# Microphone.net
KiCad netlist of a schematic drawn in Altium Designer
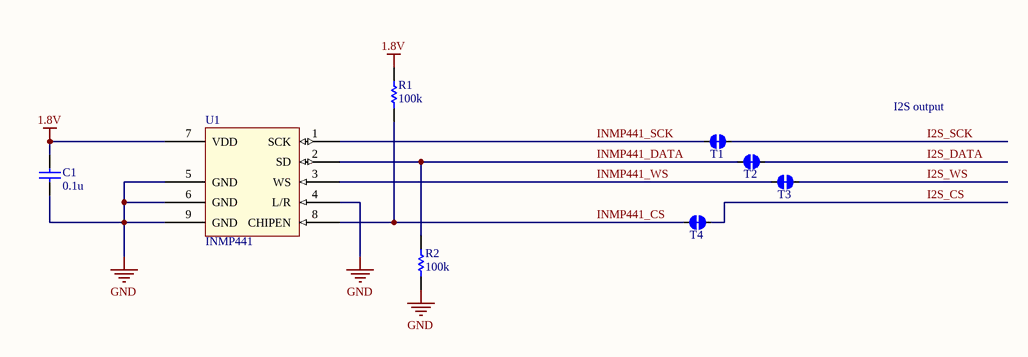
[diagram p0: Microphone.SchDoc]

(export (version "E")
  (design (tool "Eeschema 10.0.6"))
  (components
    (comp (ref "C1")
      (value "0.1u")
      (footprint "CAP0201")
      (description "Chip capacitor")
      (fields (field (name "TOLERANCE") "10%") (field (name "VOLTAGE") "6.3"))
      (libsource (lib "Hello") (part "C_0.1u_10_6.3_X5R_0201"))
    )
    (comp (ref "R1")
      (value "100k")
      (footprint "RES0201")
      (description "Chip Resistor")
      (fields (field (name "TOLERANCE") "5 %") (field (name "POWER") "0.05 W"))
      (libsource (lib "Hello") (part "R_100k_5_0.05_0201"))
    )
    (comp (ref "R2")
      (value "100k")
      (footprint "RES0201")
      (description "Chip Resistor")
      (fields (field (name "TOLERANCE") "5 %") (field (name "POWER") "0.05 W"))
      (libsource (lib "Hello") (part "R_100k_5_0.05_0201"))
    )
    (comp (ref "T1")
      (value "Solderbridge_short_1mm")
      (footprint "Solderbridge_short_1mm")
      (description "Solderbridge, shorted")
      (libsource (lib "Hello") (part "Solderbridge_short_1mm"))
    )
    (comp (ref "T2")
      (value "Solderbridge_short_1mm")
      (footprint "Solderbridge_short_1mm")
      (description "Solderbridge, shorted")
      (libsource (lib "Hello") (part "Solderbridge_short_1mm"))
    )
    (comp (ref "T3")
      (value "Solderbridge_short_1mm")
      (footprint "Solderbridge_short_1mm")
      (description "Solderbridge, shorted")
      (libsource (lib "Hello") (part "Solderbridge_short_1mm"))
    )
    (comp (ref "T4")
      (value "Solderbridge_short_1mm")
      (footprint "Solderbridge_short_1mm")
      (description "Solderbridge, shorted")
      (libsource (lib "Hello") (part "Solderbridge_short_1mm"))
    )
    (comp (ref "U1")
      (value "INMP441")
      (footprint "INMP441")
      (description "Omnidirectional digital microphone with I2S interface")
      (libsource (lib "Hello") (part "INMP441"))
    )
  )
  (nets
    (net (code "1") (name "/I2S_CS") (class "Default")
      (node (ref "T4") (pin "2") (pinfunction "2_2") (pintype "passive"))
    )
    (net (code "2") (name "/I2S_DATA") (class "Default")
      (node (ref "T2") (pin "2") (pinfunction "2_2") (pintype "passive"))
    )
    (net (code "3") (name "/I2S_SCK") (class "Default")
      (node (ref "T1") (pin "2") (pinfunction "2_2") (pintype "passive"))
    )
    (net (code "4") (name "/I2S_WS") (class "Default")
      (node (ref "T3") (pin "2") (pinfunction "2_2") (pintype "passive"))
    )
    (net (code "5") (name "/INMP441_CS") (class "Default")
      (node (ref "R1") (pin "1") (pinfunction "1_1") (pintype "passive"))
      (node (ref "T4") (pin "1") (pinfunction "1_1") (pintype "passive"))
      (node (ref "U1") (pin "8") (pinfunction "CHIPEN_8") (pintype "input"))
    )
    (net (code "6") (name "/INMP441_DATA") (class "Default")
      (node (ref "R2") (pin "2") (pinfunction "2_2") (pintype "passive"))
      (node (ref "T2") (pin "1") (pinfunction "1_1") (pintype "passive"))
      (node (ref "U1") (pin "2") (pinfunction "SD_2") (pintype "bidirectional"))
    )
    (net (code "7") (name "/INMP441_SCK") (class "Default")
      (node (ref "T1") (pin "1") (pinfunction "1_1") (pintype "passive"))
      (node (ref "U1") (pin "1") (pinfunction "SCK_1") (pintype "bidirectional"))
    )
    (net (code "8") (name "/INMP441_WS") (class "Default")
      (node (ref "T3") (pin "1") (pinfunction "1_1") (pintype "passive"))
      (node (ref "U1") (pin "3") (pinfunction "WS_3") (pintype "input"))
    )
    (net (code "9") (name "1.8V") (class "Default")
      (node (ref "C1") (pin "2") (pinfunction "2_2") (pintype "passive"))
      (node (ref "R1") (pin "2") (pinfunction "2_2") (pintype "passive"))
      (node (ref "U1") (pin "7") (pinfunction "VDD_7") (pintype "power_in"))
    )
    (net (code "10") (name "GND") (class "Default")
      (node (ref "C1") (pin "1") (pinfunction "1_1") (pintype "passive"))
      (node (ref "R2") (pin "1") (pinfunction "1_1") (pintype "passive"))
      (node (ref "U1") (pin "4") (pinfunction "L/R_4") (pintype "input"))
      (node (ref "U1") (pin "5") (pinfunction "GND_5") (pintype "power_in"))
      (node (ref "U1") (pin "6") (pinfunction "GND_6") (pintype "power_in"))
      (node (ref "U1") (pin "9") (pinfunction "GND_9") (pintype "power_in"))
    )
  )
)
